# Z80_mini.net
KiCad netlist of a schematic drawn in EAGLE
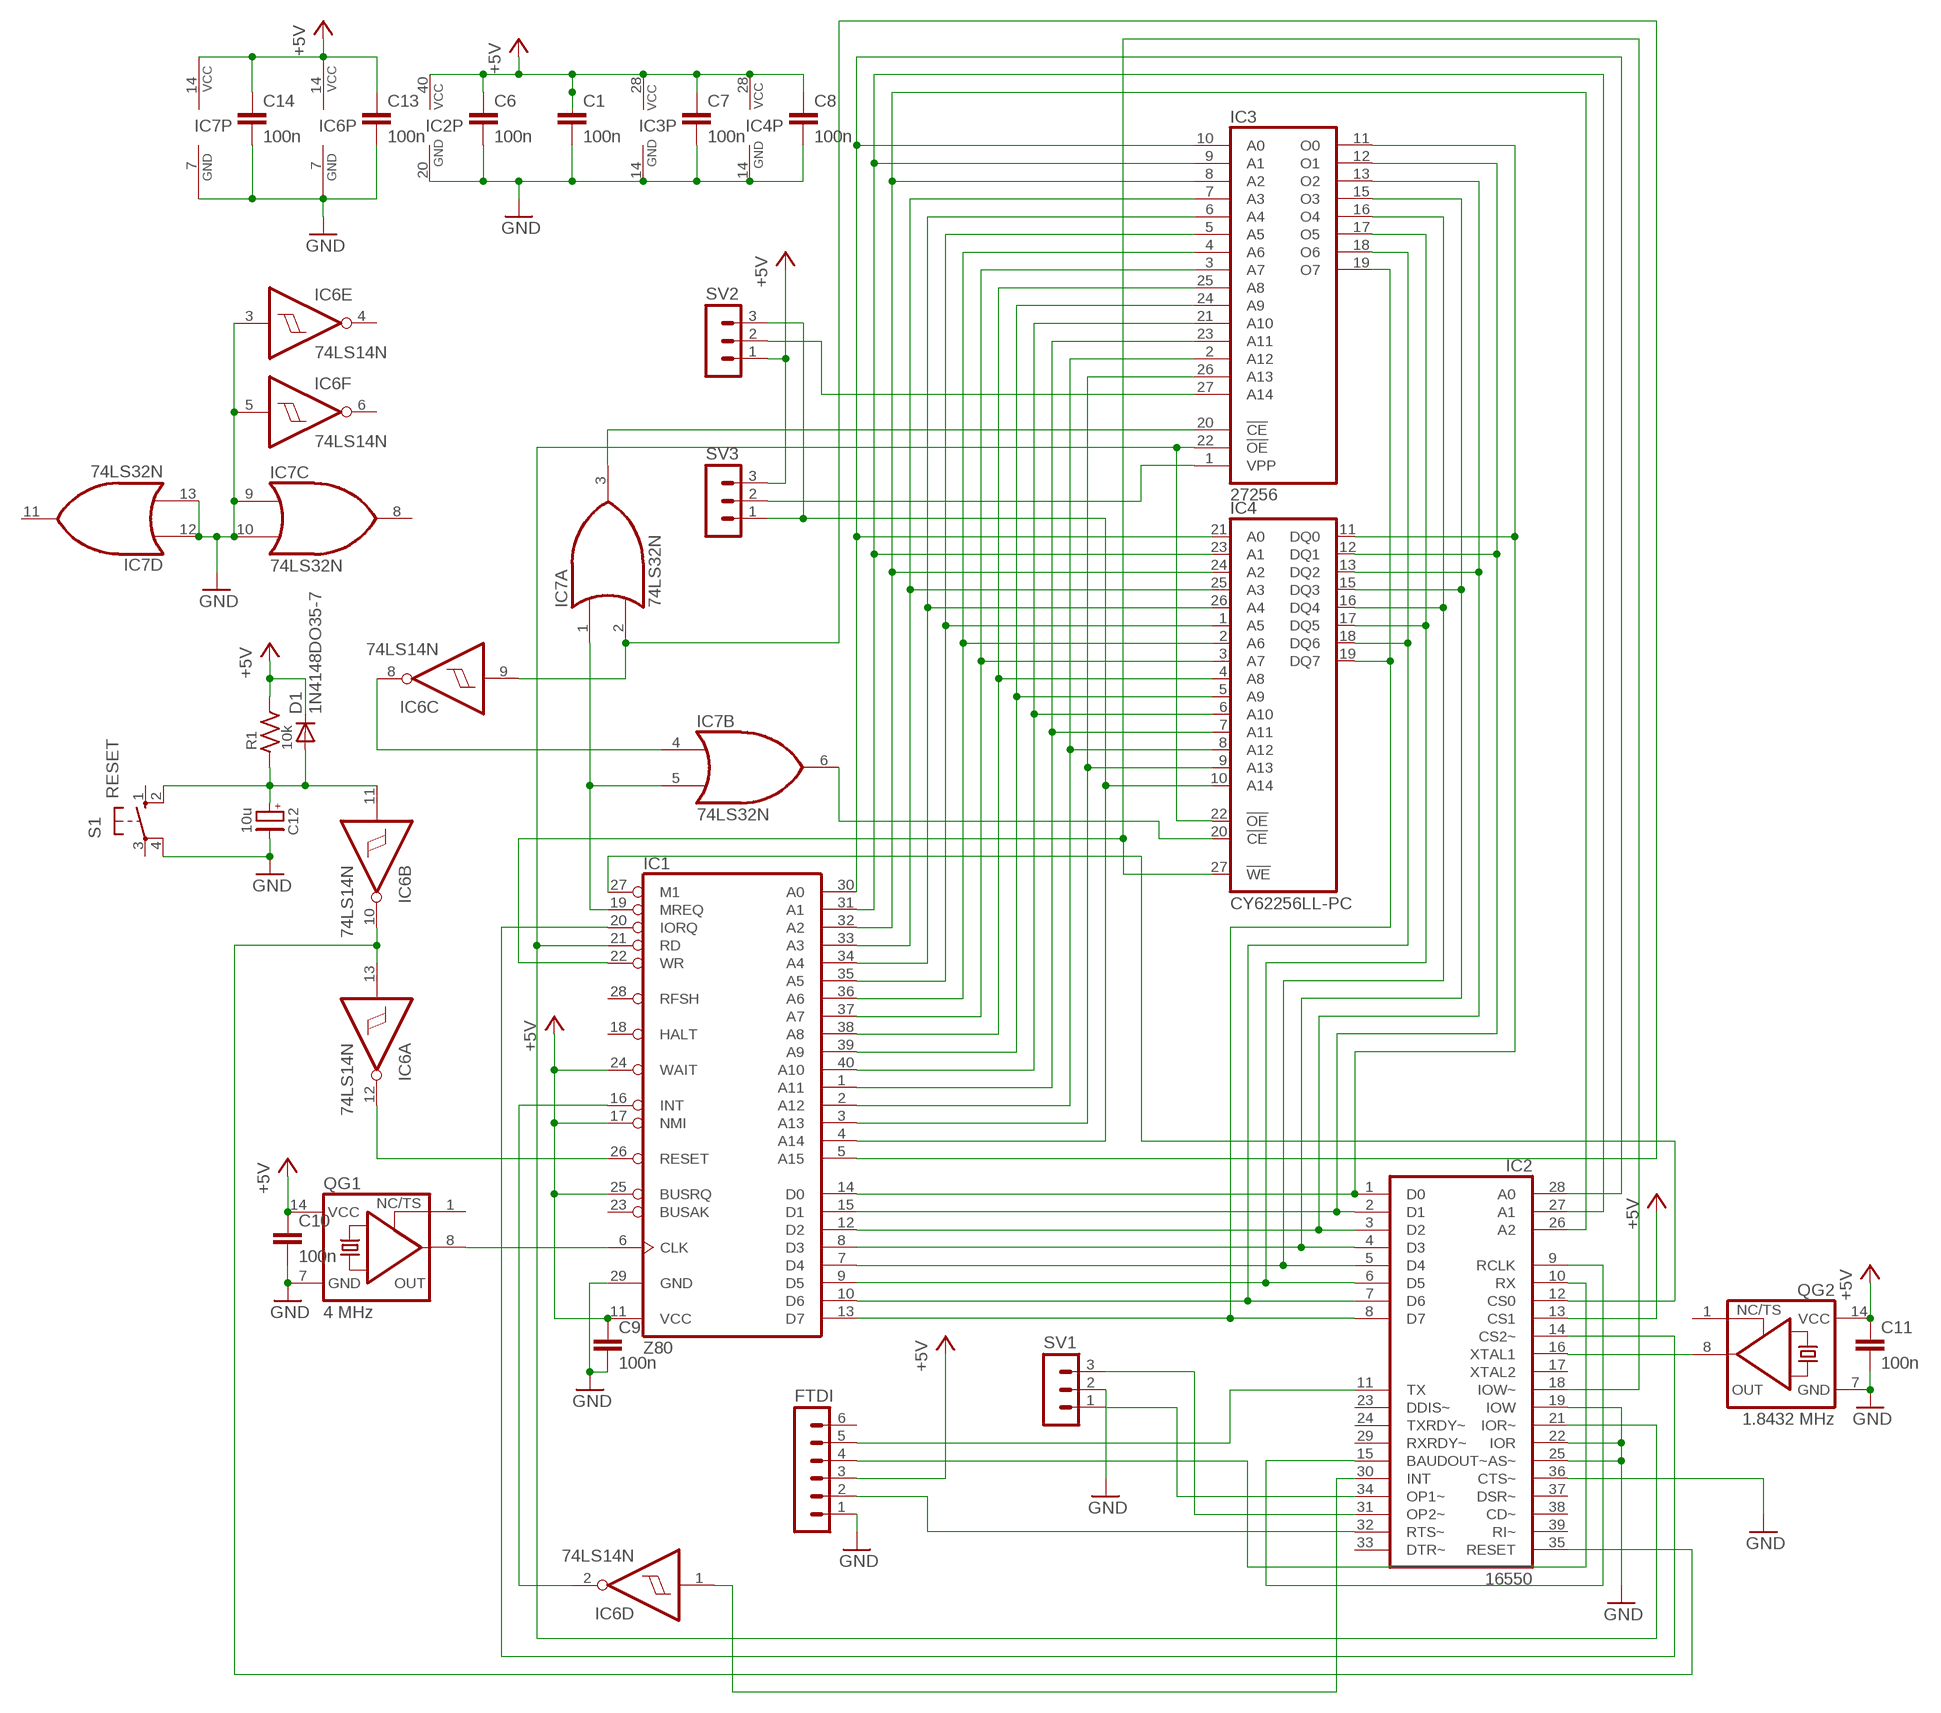
[diagram p0: schematic, sheet 1]

(export (version "E")
  (design (tool "Eeschema 10.0.6"))
  (components
    (comp (ref "C1")
      (value "100n")
      (footprint "eagle-import:C5B2.5")
      (libsource (lib "eagle-import") (part "C5/2.5"))
    )
    (comp (ref "C6")
      (value "100n")
      (footprint "eagle-import:C5B2.5")
      (libsource (lib "eagle-import") (part "C5/2.5"))
    )
    (comp (ref "C7")
      (value "100n")
      (footprint "eagle-import:C5B2.5")
      (libsource (lib "eagle-import") (part "C5/2.5"))
    )
    (comp (ref "C8")
      (value "100n")
      (footprint "eagle-import:C5B2.5")
      (libsource (lib "eagle-import") (part "C5/2.5"))
    )
    (comp (ref "C9")
      (value "100n")
      (footprint "eagle-import:C5B2.5")
      (libsource (lib "eagle-import") (part "C5/2.5"))
    )
    (comp (ref "C10")
      (value "100n")
      (footprint "eagle-import:C5B2.5")
      (libsource (lib "eagle-import") (part "C5/2.5"))
    )
    (comp (ref "C11")
      (value "100n")
      (footprint "eagle-import:C5B2.5")
      (libsource (lib "eagle-import") (part "C5/2.5"))
    )
    (comp (ref "C12")
      (value "10u")
      (footprint "eagle-import:CE01A")
      (libsource (lib "eagle-import") (part "CE01A"))
    )
    (comp (ref "C13")
      (value "100n")
      (footprint "eagle-import:C5B2.5")
      (libsource (lib "eagle-import") (part "C5/2.5"))
    )
    (comp (ref "C14")
      (value "100n")
      (footprint "eagle-import:C5B2.5")
      (libsource (lib "eagle-import") (part "C5/2.5"))
    )
    (comp (ref "D1")
      (value "1N4148DO35-7")
      (footprint "eagle-import:DO35-7")
      (libsource (lib "eagle-import") (part "1N4148DO35-7"))
    )
    (comp (ref "FTDI")
      (value "MA06-1")
      (footprint "eagle-import:MA06-1")
      (libsource (lib "eagle-import") (part "MA06-1"))
    )
    (comp (ref "IC1")
      (value "Z80")
      (footprint "eagle-import:DIL40")
      (libsource (lib "eagle-import") (part "Z80CPU"))
    )
    (comp (ref "IC2")
      (value "16550")
      (footprint "eagle-import:DIL40")
      (libsource (lib "eagle-import") (part "XR-16C550P"))
    )
    (comp (ref "IC3")
      (value "27256")
      (footprint "eagle-import:DIL28")
      (libsource (lib "eagle-import") (part "27256"))
    )
    (comp (ref "IC4")
      (value "CY62256LL-PC")
      (footprint "eagle-import:DIL28-6")
      (libsource (lib "eagle-import") (part "CY62256LL-?PC"))
    )
    (comp (ref "IC6")
      (value "74LS14N")
      (footprint "eagle-import:DIL14")
      (libsource (lib "eagle-import") (part "7414NLS"))
    )
    (comp (ref "IC7")
      (value "74LS32N")
      (footprint "eagle-import:DIL14")
      (libsource (lib "eagle-import") (part "7432NLS"))
    )
    (comp (ref "QG1")
      (value "4 MHz")
      (footprint "eagle-import:DIL14S")
      (libsource (lib "eagle-import") (part "XO-14"))
    )
    (comp (ref "QG2")
      (value "1.8432 MHz")
      (footprint "eagle-import:DIL14S")
      (libsource (lib "eagle-import") (part "XO-14"))
    )
    (comp (ref "R1")
      (value "10k")
      (footprint "eagle-import:R04N")
      (libsource (lib "eagle-import") (part "RU"))
    )
    (comp (ref "S1")
      (value "RESET")
      (footprint "eagle-import:B3F-10XX")
      (libsource (lib "eagle-import") (part "10-XX"))
    )
    (comp (ref "SV1")
      (value "MA03-1")
      (footprint "eagle-import:MA03-1")
      (libsource (lib "eagle-import") (part "MA03-1"))
    )
    (comp (ref "SV2")
      (value "MA03-1")
      (footprint "eagle-import:MA03-1")
      (libsource (lib "eagle-import") (part "MA03-1"))
    )
    (comp (ref "SV3")
      (value "MA03-1")
      (footprint "eagle-import:MA03-1")
      (libsource (lib "eagle-import") (part "MA03-1"))
    )
  )
  (nets
    (net (code "1") (name "+5V") (class "Default")
      (node (ref "C1") (pin "1") (pinfunction "1_1") (pintype "passive"))
      (node (ref "C10") (pin "1") (pinfunction "1_1") (pintype "passive"))
      (node (ref "C11") (pin "1") (pinfunction "1_1") (pintype "passive"))
      (node (ref "C13") (pin "1") (pinfunction "1_1") (pintype "passive"))
      (node (ref "C14") (pin "1") (pinfunction "1_1") (pintype "passive"))
      (node (ref "C6") (pin "1") (pinfunction "1_1") (pintype "passive"))
      (node (ref "C7") (pin "1") (pinfunction "1_1") (pintype "passive"))
      (node (ref "C8") (pin "1") (pinfunction "1_1") (pintype "passive"))
      (node (ref "C9") (pin "1") (pinfunction "1_1") (pintype "passive"))
      (node (ref "D1") (pin "C") (pinfunction "C_C") (pintype "passive"))
      (node (ref "FTDI") (pin "3") (pinfunction "3_3") (pintype "passive"))
      (node (ref "IC1") (pin "11") (pinfunction "VCC_11") (pintype "power_in"))
      (node (ref "IC1") (pin "17") (pinfunction "NMI_17") (pintype "input"))
      (node (ref "IC1") (pin "24") (pinfunction "WAIT_24") (pintype "input"))
      (node (ref "IC1") (pin "25") (pinfunction "BUSRQ_25") (pintype "input"))
      (node (ref "IC2") (pin "13") (pinfunction "CS1_13") (pintype "input"))
      (node (ref "IC2") (pin "40") (pinfunction "VCC_40") (pintype "power_in"))
      (node (ref "IC3") (pin "28") (pinfunction "VCC_28") (pintype "power_in"))
      (node (ref "IC4") (pin "28") (pinfunction "VCC_28") (pintype "power_in"))
      (node (ref "IC6") (pin "14") (pinfunction "VCC_14") (pintype "power_in"))
      (node (ref "IC7") (pin "14") (pinfunction "VCC_14") (pintype "power_in"))
      (node (ref "QG1") (pin "14") (pinfunction "VCC_14") (pintype "power_in"))
      (node (ref "QG2") (pin "14") (pinfunction "VCC_14") (pintype "power_in"))
      (node (ref "R1") (pin "2") (pinfunction "2_2") (pintype "passive"))
      (node (ref "SV2") (pin "1") (pinfunction "1_1") (pintype "passive"))
      (node (ref "SV3") (pin "3") (pinfunction "3_3") (pintype "passive"))
    )
    (net (code "2") (name "GND") (class "Default")
      (node (ref "C1") (pin "2") (pinfunction "2_2") (pintype "passive"))
      (node (ref "C10") (pin "2") (pinfunction "2_2") (pintype "passive"))
      (node (ref "C11") (pin "2") (pinfunction "2_2") (pintype "passive"))
      (node (ref "C12") (pin "-") (pinfunction "-_-") (pintype "passive"))
      (node (ref "C13") (pin "2") (pinfunction "2_2") (pintype "passive"))
      (node (ref "C14") (pin "2") (pinfunction "2_2") (pintype "passive"))
      (node (ref "C6") (pin "2") (pinfunction "2_2") (pintype "passive"))
      (node (ref "C7") (pin "2") (pinfunction "2_2") (pintype "passive"))
      (node (ref "C8") (pin "2") (pinfunction "2_2") (pintype "passive"))
      (node (ref "C9") (pin "2") (pinfunction "2_2") (pintype "passive"))
      (node (ref "FTDI") (pin "1") (pinfunction "1_1") (pintype "passive"))
      (node (ref "IC1") (pin "29") (pinfunction "GND_29") (pintype "power_in"))
      (node (ref "IC2") (pin "19") (pinfunction "IOW_19") (pintype "input"))
      (node (ref "IC2") (pin "20") (pinfunction "GND_20") (pintype "power_in"))
      (node (ref "IC2") (pin "22") (pinfunction "IOR_22") (pintype "input"))
      (node (ref "IC2") (pin "25") (pinfunction "AS~{}_25") (pintype "input"))
      (node (ref "IC2") (pin "36") (pinfunction "CTS~{}_36") (pintype "input"))
      (node (ref "IC3") (pin "14") (pinfunction "GND_14") (pintype "power_in"))
      (node (ref "IC4") (pin "14") (pinfunction "GND_14") (pintype "power_in"))
      (node (ref "IC6") (pin "3") (pinfunction "I_3") (pintype "input"))
      (node (ref "IC6") (pin "5") (pinfunction "I_5") (pintype "input"))
      (node (ref "IC6") (pin "7") (pinfunction "GND_7") (pintype "power_in"))
      (node (ref "IC7") (pin "10") (pinfunction "I1_10") (pintype "input"))
      (node (ref "IC7") (pin "12") (pinfunction "I0_12") (pintype "input"))
      (node (ref "IC7") (pin "13") (pinfunction "I1_13") (pintype "input"))
      (node (ref "IC7") (pin "7") (pinfunction "GND_7") (pintype "power_in"))
      (node (ref "IC7") (pin "9") (pinfunction "I0_9") (pintype "input"))
      (node (ref "QG1") (pin "7") (pinfunction "GND_7") (pintype "power_in"))
      (node (ref "QG2") (pin "7") (pinfunction "GND_7") (pintype "power_in"))
      (node (ref "S1") (pin "4") (pinfunction "P1_4") (pintype "passive"))
      (node (ref "SV1") (pin "2") (pinfunction "2_2") (pintype "passive"))
    )
    (net (code "3") (name "Net-(IC1-A0)") (class "Default")
      (node (ref "IC1") (pin "30") (pinfunction "A0_30") (pintype "output"))
      (node (ref "IC2") (pin "28") (pinfunction "A0_28") (pintype "input"))
      (node (ref "IC3") (pin "10") (pinfunction "A0_10") (pintype "input"))
      (node (ref "IC4") (pin "21") (pinfunction "A0_21") (pintype "input"))
    )
    (net (code "4") (name "Net-(IC1-A1)") (class "Default")
      (node (ref "IC1") (pin "31") (pinfunction "A1_31") (pintype "output"))
      (node (ref "IC2") (pin "27") (pinfunction "A1_27") (pintype "input"))
      (node (ref "IC3") (pin "9") (pinfunction "A1_9") (pintype "input"))
      (node (ref "IC4") (pin "23") (pinfunction "A1_23") (pintype "input"))
    )
    (net (code "5") (name "Net-(IC1-A2)") (class "Default")
      (node (ref "IC1") (pin "32") (pinfunction "A2_32") (pintype "output"))
      (node (ref "IC2") (pin "26") (pinfunction "A2_26") (pintype "input"))
      (node (ref "IC3") (pin "8") (pinfunction "A2_8") (pintype "input"))
      (node (ref "IC4") (pin "24") (pinfunction "A2_24") (pintype "input"))
    )
    (net (code "6") (name "Net-(IC1-A3)") (class "Default")
      (node (ref "IC1") (pin "33") (pinfunction "A3_33") (pintype "output"))
      (node (ref "IC3") (pin "7") (pinfunction "A3_7") (pintype "input"))
      (node (ref "IC4") (pin "25") (pinfunction "A3_25") (pintype "input"))
    )
    (net (code "7") (name "Net-(IC1-A4)") (class "Default")
      (node (ref "IC1") (pin "34") (pinfunction "A4_34") (pintype "output"))
      (node (ref "IC3") (pin "6") (pinfunction "A4_6") (pintype "input"))
      (node (ref "IC4") (pin "26") (pinfunction "A4_26") (pintype "input"))
    )
    (net (code "8") (name "Net-(IC1-A5)") (class "Default")
      (node (ref "IC1") (pin "35") (pinfunction "A5_35") (pintype "output"))
      (node (ref "IC3") (pin "5") (pinfunction "A5_5") (pintype "input"))
      (node (ref "IC4") (pin "1") (pinfunction "A5_1") (pintype "input"))
    )
    (net (code "9") (name "Net-(IC1-A6)") (class "Default")
      (node (ref "IC1") (pin "36") (pinfunction "A6_36") (pintype "output"))
      (node (ref "IC3") (pin "4") (pinfunction "A6_4") (pintype "input"))
      (node (ref "IC4") (pin "2") (pinfunction "A6_2") (pintype "input"))
    )
    (net (code "10") (name "Net-(IC1-A7)") (class "Default")
      (node (ref "IC1") (pin "37") (pinfunction "A7_37") (pintype "output"))
      (node (ref "IC3") (pin "3") (pinfunction "A7_3") (pintype "input"))
      (node (ref "IC4") (pin "3") (pinfunction "A7_3") (pintype "input"))
    )
    (net (code "11") (name "Net-(IC1-A8)") (class "Default")
      (node (ref "IC1") (pin "38") (pinfunction "A8_38") (pintype "output"))
      (node (ref "IC3") (pin "25") (pinfunction "A8_25") (pintype "input"))
      (node (ref "IC4") (pin "4") (pinfunction "A8_4") (pintype "input"))
    )
    (net (code "12") (name "Net-(IC1-A9)") (class "Default")
      (node (ref "IC1") (pin "39") (pinfunction "A9_39") (pintype "output"))
      (node (ref "IC3") (pin "24") (pinfunction "A9_24") (pintype "input"))
      (node (ref "IC4") (pin "5") (pinfunction "A9_5") (pintype "input"))
    )
    (net (code "13") (name "Net-(IC1-A10)") (class "Default")
      (node (ref "IC1") (pin "40") (pinfunction "A10_40") (pintype "output"))
      (node (ref "IC3") (pin "21") (pinfunction "A10_21") (pintype "input"))
      (node (ref "IC4") (pin "6") (pinfunction "A10_6") (pintype "input"))
    )
    (net (code "14") (name "Net-(IC1-A11)") (class "Default")
      (node (ref "IC1") (pin "1") (pinfunction "A11_1") (pintype "output"))
      (node (ref "IC3") (pin "23") (pinfunction "A11_23") (pintype "input"))
      (node (ref "IC4") (pin "7") (pinfunction "A11_7") (pintype "input"))
    )
    (net (code "15") (name "Net-(IC1-A12)") (class "Default")
      (node (ref "IC1") (pin "2") (pinfunction "A12_2") (pintype "output"))
      (node (ref "IC3") (pin "2") (pinfunction "A12_2") (pintype "input"))
      (node (ref "IC4") (pin "8") (pinfunction "A12_8") (pintype "input"))
    )
    (net (code "16") (name "Net-(IC1-A13)") (class "Default")
      (node (ref "IC1") (pin "3") (pinfunction "A13_3") (pintype "output"))
      (node (ref "IC3") (pin "26") (pinfunction "A13_26") (pintype "input"))
      (node (ref "IC4") (pin "9") (pinfunction "A13_9") (pintype "input"))
    )
    (net (code "17") (name "Net-(IC1-A14)") (class "Default")
      (node (ref "IC1") (pin "4") (pinfunction "A14_4") (pintype "output"))
      (node (ref "IC4") (pin "10") (pinfunction "A14_10") (pintype "input"))
      (node (ref "SV2") (pin "3") (pinfunction "3_3") (pintype "passive"))
      (node (ref "SV3") (pin "1") (pinfunction "1_1") (pintype "passive"))
    )
    (net (code "18") (name "Net-(IC1-A15)") (class "Default")
      (node (ref "IC1") (pin "5") (pinfunction "A15_5") (pintype "output"))
      (node (ref "IC6") (pin "9") (pinfunction "I_9") (pintype "input"))
      (node (ref "IC7") (pin "2") (pinfunction "I1_2") (pintype "input"))
    )
    (net (code "19") (name "Net-(IC1-CLK)") (class "Default")
      (node (ref "IC1") (pin "6") (pinfunction "CLK_6") (pintype "input"))
      (node (ref "QG1") (pin "8") (pinfunction "OUT_8") (pintype "output"))
    )
    (net (code "20") (name "Net-(IC1-D0)") (class "Default")
      (node (ref "IC1") (pin "14") (pinfunction "D0_14") (pintype "bidirectional"))
      (node (ref "IC2") (pin "1") (pinfunction "D0_1") (pintype "bidirectional"))
      (node (ref "IC3") (pin "11") (pinfunction "O0_11") (pintype "tri_state"))
      (node (ref "IC4") (pin "11") (pinfunction "DQ0_11") (pintype "bidirectional"))
    )
    (net (code "21") (name "Net-(IC1-D1)") (class "Default")
      (node (ref "IC1") (pin "15") (pinfunction "D1_15") (pintype "bidirectional"))
      (node (ref "IC2") (pin "2") (pinfunction "D1_2") (pintype "bidirectional"))
      (node (ref "IC3") (pin "12") (pinfunction "O1_12") (pintype "tri_state"))
      (node (ref "IC4") (pin "12") (pinfunction "DQ1_12") (pintype "bidirectional"))
    )
    (net (code "22") (name "Net-(IC1-D2)") (class "Default")
      (node (ref "IC1") (pin "12") (pinfunction "D2_12") (pintype "bidirectional"))
      (node (ref "IC2") (pin "3") (pinfunction "D2_3") (pintype "bidirectional"))
      (node (ref "IC3") (pin "13") (pinfunction "O2_13") (pintype "tri_state"))
      (node (ref "IC4") (pin "13") (pinfunction "DQ2_13") (pintype "bidirectional"))
    )
    (net (code "23") (name "Net-(IC1-D3)") (class "Default")
      (node (ref "IC1") (pin "8") (pinfunction "D3_8") (pintype "bidirectional"))
      (node (ref "IC2") (pin "4") (pinfunction "D3_4") (pintype "bidirectional"))
      (node (ref "IC3") (pin "15") (pinfunction "O3_15") (pintype "tri_state"))
      (node (ref "IC4") (pin "15") (pinfunction "DQ3_15") (pintype "bidirectional"))
    )
    (net (code "24") (name "Net-(IC1-D4)") (class "Default")
      (node (ref "IC1") (pin "7") (pinfunction "D4_7") (pintype "bidirectional"))
      (node (ref "IC2") (pin "5") (pinfunction "D4_5") (pintype "bidirectional"))
      (node (ref "IC3") (pin "16") (pinfunction "O4_16") (pintype "tri_state"))
      (node (ref "IC4") (pin "16") (pinfunction "DQ4_16") (pintype "bidirectional"))
    )
    (net (code "25") (name "Net-(IC1-D5)") (class "Default")
      (node (ref "IC1") (pin "9") (pinfunction "D5_9") (pintype "bidirectional"))
      (node (ref "IC2") (pin "6") (pinfunction "D5_6") (pintype "bidirectional"))
      (node (ref "IC3") (pin "17") (pinfunction "O5_17") (pintype "tri_state"))
      (node (ref "IC4") (pin "17") (pinfunction "DQ5_17") (pintype "bidirectional"))
    )
    (net (code "26") (name "Net-(IC1-D6)") (class "Default")
      (node (ref "IC1") (pin "10") (pinfunction "D6_10") (pintype "bidirectional"))
      (node (ref "IC2") (pin "7") (pinfunction "D6_7") (pintype "bidirectional"))
      (node (ref "IC3") (pin "18") (pinfunction "O6_18") (pintype "tri_state"))
      (node (ref "IC4") (pin "18") (pinfunction "DQ6_18") (pintype "bidirectional"))
    )
    (net (code "27") (name "Net-(IC1-D7)") (class "Default")
      (node (ref "IC1") (pin "13") (pinfunction "D7_13") (pintype "bidirectional"))
      (node (ref "IC2") (pin "8") (pinfunction "D7_8") (pintype "bidirectional"))
      (node (ref "IC3") (pin "19") (pinfunction "O7_19") (pintype "tri_state"))
      (node (ref "IC4") (pin "19") (pinfunction "DQ7_19") (pintype "bidirectional"))
    )
    (net (code "28") (name "Net-(IC1-INT)") (class "Default")
      (node (ref "IC1") (pin "16") (pinfunction "INT_16") (pintype "input"))
      (node (ref "IC6") (pin "2") (pinfunction "O_2") (pintype "output"))
    )
    (net (code "29") (name "Net-(IC1-IORQ)") (class "Default")
      (node (ref "IC1") (pin "20") (pinfunction "IORQ_20") (pintype "output"))
      (node (ref "IC2") (pin "14") (pinfunction "CS2~{}_14") (pintype "input"))
    )
    (net (code "30") (name "Net-(IC1-M1)") (class "Default")
      (node (ref "IC1") (pin "27") (pinfunction "M1_27") (pintype "output"))
      (node (ref "IC2") (pin "12") (pinfunction "CS0_12") (pintype "input"))
    )
    (net (code "31") (name "Net-(IC1-MREQ)") (class "Default")
      (node (ref "IC1") (pin "19") (pinfunction "MREQ_19") (pintype "output"))
      (node (ref "IC7") (pin "1") (pinfunction "I0_1") (pintype "input"))
      (node (ref "IC7") (pin "5") (pinfunction "I1_5") (pintype "input"))
    )
    (net (code "32") (name "Net-(IC1-RD)") (class "Default")
      (node (ref "IC1") (pin "21") (pinfunction "RD_21") (pintype "output"))
      (node (ref "IC2") (pin "21") (pinfunction "IOR~{}_21") (pintype "input"))
      (node (ref "IC3") (pin "22") (pinfunction "~{OE}_22") (pintype "input"))
      (node (ref "IC4") (pin "22") (pinfunction "~{OE}_22") (pintype "input"))
    )
    (net (code "33") (name "Net-(IC1-RESET)") (class "Default")
      (node (ref "IC1") (pin "26") (pinfunction "RESET_26") (pintype "input"))
      (node (ref "IC6") (pin "12") (pinfunction "O_12") (pintype "output"))
    )
    (net (code "34") (name "Net-(IC1-WR)") (class "Default")
      (node (ref "IC1") (pin "22") (pinfunction "WR_22") (pintype "output"))
      (node (ref "IC2") (pin "18") (pinfunction "IOW~{}_18") (pintype "input"))
      (node (ref "IC4") (pin "27") (pinfunction "~{WE}_27") (pintype "input"))
    )
    (net (code "35") (name "Net-(IC2A-BAUDOUT~{})") (class "Default")
      (node (ref "IC2") (pin "15") (pinfunction "BAUDOUT~{}_15") (pintype "output"))
      (node (ref "IC2") (pin "9") (pinfunction "RCLK_9") (pintype "input"))
    )
    (net (code "36") (name "Net-(IC2A-INT)") (class "Default")
      (node (ref "IC2") (pin "30") (pinfunction "INT_30") (pintype "output"))
      (node (ref "IC6") (pin "1") (pinfunction "I_1") (pintype "input"))
    )
    (net (code "37") (name "Net-(IC2A-OP1~{})") (class "Default")
      (node (ref "IC2") (pin "34") (pinfunction "OP1~{}_34") (pintype "output"))
      (node (ref "SV1") (pin "1") (pinfunction "1_1") (pintype "passive"))
    )
    (net (code "38") (name "Net-(IC2A-OP2~{})") (class "Default")
      (node (ref "IC2") (pin "31") (pinfunction "OP2~{}_31") (pintype "output"))
      (node (ref "SV1") (pin "3") (pinfunction "3_3") (pintype "passive"))
    )
    (net (code "39") (name "Net-(IC2A-RESET)") (class "Default")
      (node (ref "IC2") (pin "35") (pinfunction "RESET_35") (pintype "input"))
      (node (ref "IC6") (pin "10") (pinfunction "O_10") (pintype "output"))
      (node (ref "IC6") (pin "13") (pinfunction "I_13") (pintype "input"))
    )
    (net (code "40") (name "Net-(IC2A-RTS~{})") (class "Default")
      (node (ref "FTDI") (pin "2") (pinfunction "2_2") (pintype "passive"))
      (node (ref "IC2") (pin "32") (pinfunction "RTS~{}_32") (pintype "output"))
    )
    (net (code "41") (name "Net-(IC2A-RX)") (class "Default")
      (node (ref "FTDI") (pin "4") (pinfunction "4_4") (pintype "passive"))
      (node (ref "IC2") (pin "10") (pinfunction "RX_10") (pintype "input"))
    )
    (net (code "42") (name "Net-(IC2A-TX)") (class "Default")
      (node (ref "FTDI") (pin "5") (pinfunction "5_5") (pintype "passive"))
      (node (ref "IC2") (pin "11") (pinfunction "TX_11") (pintype "output"))
    )
    (net (code "43") (name "Net-(IC2A-XTAL1)") (class "Default")
      (node (ref "IC2") (pin "16") (pinfunction "XTAL1_16") (pintype "input"))
      (node (ref "QG2") (pin "8") (pinfunction "OUT_8") (pintype "output"))
    )
    (net (code "44") (name "Net-(IC3A-A14)") (class "Default")
      (node (ref "IC3") (pin "27") (pinfunction "A14_27") (pintype "input"))
      (node (ref "SV2") (pin "2") (pinfunction "2_2") (pintype "passive"))
    )
    (net (code "45") (name "Net-(IC3A-VPP)") (class "Default")
      (node (ref "IC3") (pin "1") (pinfunction "VPP_1") (pintype "input"))
      (node (ref "SV3") (pin "2") (pinfunction "2_2") (pintype "passive"))
    )
    (net (code "46") (name "Net-(IC3A-~{CE})") (class "Default")
      (node (ref "IC3") (pin "20") (pinfunction "~{CE}_20") (pintype "input"))
      (node (ref "IC7") (pin "3") (pinfunction "O_3") (pintype "output"))
    )
    (net (code "47") (name "Net-(IC4A-~{CE})") (class "Default")
      (node (ref "IC4") (pin "20") (pinfunction "~{CE}_20") (pintype "input"))
      (node (ref "IC7") (pin "6") (pinfunction "O_6") (pintype "output"))
    )
    (net (code "48") (name "Net-(IC6B-I)") (class "Default")
      (node (ref "C12") (pin "+") (pinfunction "+_+") (pintype "passive"))
      (node (ref "D1") (pin "A") (pinfunction "A_A") (pintype "passive"))
      (node (ref "IC6") (pin "11") (pinfunction "I_11") (pintype "input"))
      (node (ref "R1") (pin "1") (pinfunction "1_1") (pintype "passive"))
      (node (ref "S1") (pin "2") (pinfunction "S1_2") (pintype "passive"))
    )
    (net (code "49") (name "Net-(IC6C-O)") (class "Default")
      (node (ref "IC6") (pin "8") (pinfunction "O_8") (pintype "output"))
      (node (ref "IC7") (pin "4") (pinfunction "I0_4") (pintype "input"))
    )
    (net (code "50") (name "unconnected-(FTDI-Pad6)") (class "Default")
      (node (ref "FTDI") (pin "6") (pinfunction "6_6") (pintype "passive"))
    )
    (net (code "51") (name "unconnected-(IC1-BUSAK-Pad23)") (class "Default")
      (node (ref "IC1") (pin "23") (pinfunction "BUSAK_23") (pintype "output"))
    )
    (net (code "52") (name "unconnected-(IC1-HALT-Pad18)") (class "Default")
      (node (ref "IC1") (pin "18") (pinfunction "HALT_18") (pintype "output"))
    )
    (net (code "53") (name "unconnected-(IC1-RFSH-Pad28)") (class "Default")
      (node (ref "IC1") (pin "28") (pinfunction "RFSH_28") (pintype "output"))
    )
    (net (code "54") (name "unconnected-(IC2A-CD~{}-Pad38)") (class "Default")
      (node (ref "IC2") (pin "38") (pinfunction "CD~{}_38") (pintype "input"))
    )
    (net (code "55") (name "unconnected-(IC2A-DDIS~{}-Pad23)") (class "Default")
      (node (ref "IC2") (pin "23") (pinfunction "DDIS~{}_23") (pintype "output"))
    )
    (net (code "56") (name "unconnected-(IC2A-DSR~{}-Pad37)") (class "Default")
      (node (ref "IC2") (pin "37") (pinfunction "DSR~{}_37") (pintype "input"))
    )
    (net (code "57") (name "unconnected-(IC2A-DTR~{}-Pad33)") (class "Default")
      (node (ref "IC2") (pin "33") (pinfunction "DTR~{}_33") (pintype "output"))
    )
    (net (code "58") (name "unconnected-(IC2A-RI~{}-Pad39)") (class "Default")
      (node (ref "IC2") (pin "39") (pinfunction "RI~{}_39") (pintype "input"))
    )
    (net (code "59") (name "unconnected-(IC2A-RXRDY~{}-Pad29)") (class "Default")
      (node (ref "IC2") (pin "29") (pinfunction "RXRDY~{}_29") (pintype "output"))
    )
    (net (code "60") (name "unconnected-(IC2A-TXRDY~{}-Pad24)") (class "Default")
      (node (ref "IC2") (pin "24") (pinfunction "TXRDY~{}_24") (pintype "output"))
    )
    (net (code "61") (name "unconnected-(IC2A-XTAL2-Pad17)") (class "Default")
      (node (ref "IC2") (pin "17") (pinfunction "XTAL2_17") (pintype "input"))
    )
    (net (code "62") (name "unconnected-(IC6E-O-Pad4)") (class "Default")
      (node (ref "IC6") (pin "4") (pinfunction "O_4") (pintype "output"))
    )
    (net (code "63") (name "unconnected-(IC6F-O-Pad6)") (class "Default")
      (node (ref "IC6") (pin "6") (pinfunction "O_6") (pintype "output"))
    )
    (net (code "64") (name "unconnected-(IC7C-O-Pad8)") (class "Default")
      (node (ref "IC7") (pin "8") (pinfunction "O_8") (pintype "output"))
    )
    (net (code "65") (name "unconnected-(IC7D-O-Pad11)") (class "Default")
      (node (ref "IC7") (pin "11") (pinfunction "O_11") (pintype "output"))
    )
    (net (code "66") (name "unconnected-(QG1-TS-Pad1)") (class "Default")
      (node (ref "QG1") (pin "1") (pinfunction "TS_1") (pintype "passive"))
    )
    (net (code "67") (name "unconnected-(QG2-TS-Pad1)") (class "Default")
      (node (ref "QG2") (pin "1") (pinfunction "TS_1") (pintype "passive"))
    )
    (net (code "68") (name "unconnected-(S1-P-Pad3)") (class "Default")
      (node (ref "S1") (pin "3") (pinfunction "P_3") (pintype "passive"))
    )
    (net (code "69") (name "unconnected-(S1-S-Pad1)") (class "Default")
      (node (ref "S1") (pin "1") (pinfunction "S_1") (pintype "passive"))
    )
  )
)
